# LCD.net
KiCad netlist of a schematic drawn in Altium Designer
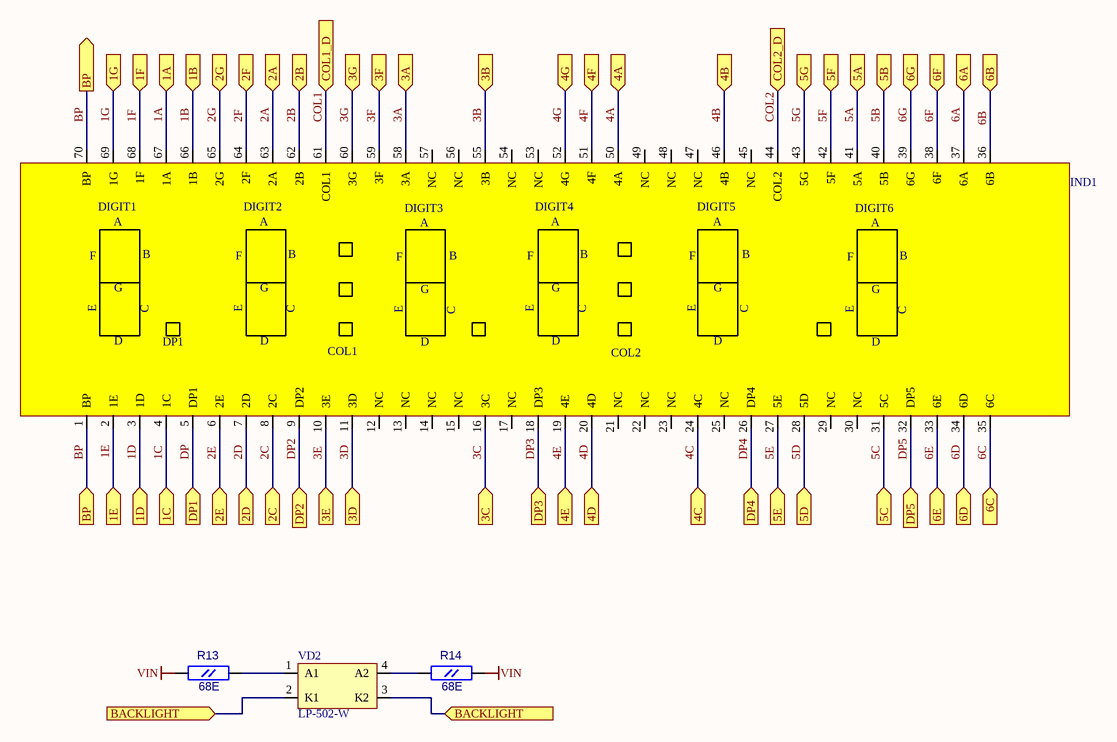
[diagram p0: LCD.SchDoc]

(export (version "E")
  (design (tool "Eeschema 10.0.6"))
  (components
    (comp (ref "IND1")
      (value "DE156")
      (footprint "IND_DE156")
      (description "6digit 7Segment indicator")
      (libsource (lib "gprs_modem_2") (part "IND7_DE156"))
    )
    (comp (ref "R13")
      (value "68E")
      (footprint "RC0603")
      (description "RC0603")
      (libsource (lib "gprs_modem_2") (part "RC0603"))
    )
    (comp (ref "R14")
      (value "68E")
      (footprint "RC0603")
      (description "RC0603")
      (libsource (lib "gprs_modem_2") (part "RC0603"))
    )
    (comp (ref "VD2")
      (value "LP-502-W")
      (footprint "LP-502-W")
      (description "Backlight for lcd display")
      (libsource (lib "gprs_modem_2") (part "LP-502-W"))
    )
  )
  (nets
    (net (code "1") (name "/1A") (class "Default")
      (node (ref "IND1") (pin "67") (pinfunction "1A_67") (pintype "passive"))
    )
    (net (code "2") (name "/1B") (class "Default")
      (node (ref "IND1") (pin "66") (pinfunction "1B_66") (pintype "passive"))
    )
    (net (code "3") (name "/1C") (class "Default")
      (node (ref "IND1") (pin "4") (pinfunction "1C_4") (pintype "passive"))
    )
    (net (code "4") (name "/1D") (class "Default")
      (node (ref "IND1") (pin "3") (pinfunction "1D_3") (pintype "passive"))
    )
    (net (code "5") (name "/1E") (class "Default")
      (node (ref "IND1") (pin "2") (pinfunction "1E_2") (pintype "passive"))
    )
    (net (code "6") (name "/1F") (class "Default")
      (node (ref "IND1") (pin "68") (pinfunction "1F_68") (pintype "passive"))
    )
    (net (code "7") (name "/1G") (class "Default")
      (node (ref "IND1") (pin "69") (pinfunction "1G_69") (pintype "passive"))
    )
    (net (code "8") (name "/2A") (class "Default")
      (node (ref "IND1") (pin "63") (pinfunction "2A_63") (pintype "passive"))
    )
    (net (code "9") (name "/2B") (class "Default")
      (node (ref "IND1") (pin "62") (pinfunction "2B_62") (pintype "passive"))
    )
    (net (code "10") (name "/2C") (class "Default")
      (node (ref "IND1") (pin "8") (pinfunction "2C_8") (pintype "passive"))
    )
    (net (code "11") (name "/2D") (class "Default")
      (node (ref "IND1") (pin "7") (pinfunction "2D_7") (pintype "passive"))
    )
    (net (code "12") (name "/2E") (class "Default")
      (node (ref "IND1") (pin "6") (pinfunction "2E_6") (pintype "passive"))
    )
    (net (code "13") (name "/2F") (class "Default")
      (node (ref "IND1") (pin "64") (pinfunction "2F_64") (pintype "passive"))
    )
    (net (code "14") (name "/2G") (class "Default")
      (node (ref "IND1") (pin "65") (pinfunction "2G_65") (pintype "passive"))
    )
    (net (code "15") (name "/3A") (class "Default")
      (node (ref "IND1") (pin "58") (pinfunction "3A_58") (pintype "passive"))
    )
    (net (code "16") (name "/3B") (class "Default")
      (node (ref "IND1") (pin "55") (pinfunction "3B_55") (pintype "passive"))
    )
    (net (code "17") (name "/3C") (class "Default")
      (node (ref "IND1") (pin "16") (pinfunction "3C_16") (pintype "passive"))
    )
    (net (code "18") (name "/3D") (class "Default")
      (node (ref "IND1") (pin "11") (pinfunction "3D_11") (pintype "passive"))
    )
    (net (code "19") (name "/3E") (class "Default")
      (node (ref "IND1") (pin "10") (pinfunction "3E_10") (pintype "passive"))
    )
    (net (code "20") (name "/3F") (class "Default")
      (node (ref "IND1") (pin "59") (pinfunction "3F_59") (pintype "passive"))
    )
    (net (code "21") (name "/3G") (class "Default")
      (node (ref "IND1") (pin "60") (pinfunction "3G_60") (pintype "passive"))
    )
    (net (code "22") (name "/4A") (class "Default")
      (node (ref "IND1") (pin "50") (pinfunction "4A_50") (pintype "passive"))
    )
    (net (code "23") (name "/4B") (class "Default")
      (node (ref "IND1") (pin "46") (pinfunction "4B_46") (pintype "passive"))
    )
    (net (code "24") (name "/4C") (class "Default")
      (node (ref "IND1") (pin "24") (pinfunction "4C_24") (pintype "passive"))
    )
    (net (code "25") (name "/4D") (class "Default")
      (node (ref "IND1") (pin "20") (pinfunction "4D_20") (pintype "passive"))
    )
    (net (code "26") (name "/4E") (class "Default")
      (node (ref "IND1") (pin "19") (pinfunction "4E_19") (pintype "passive"))
    )
    (net (code "27") (name "/4F") (class "Default")
      (node (ref "IND1") (pin "51") (pinfunction "4F_51") (pintype "passive"))
    )
    (net (code "28") (name "/4G") (class "Default")
      (node (ref "IND1") (pin "52") (pinfunction "4G_52") (pintype "passive"))
    )
    (net (code "29") (name "/5A") (class "Default")
      (node (ref "IND1") (pin "41") (pinfunction "5A_41") (pintype "passive"))
    )
    (net (code "30") (name "/5B") (class "Default")
      (node (ref "IND1") (pin "40") (pinfunction "5B_40") (pintype "passive"))
    )
    (net (code "31") (name "/5C") (class "Default")
      (node (ref "IND1") (pin "31") (pinfunction "5C_31") (pintype "passive"))
    )
    (net (code "32") (name "/5D") (class "Default")
      (node (ref "IND1") (pin "28") (pinfunction "5D_28") (pintype "passive"))
    )
    (net (code "33") (name "/5E") (class "Default")
      (node (ref "IND1") (pin "27") (pinfunction "5E_27") (pintype "passive"))
    )
    (net (code "34") (name "/5F") (class "Default")
      (node (ref "IND1") (pin "42") (pinfunction "5F_42") (pintype "passive"))
    )
    (net (code "35") (name "/5G") (class "Default")
      (node (ref "IND1") (pin "43") (pinfunction "5G_43") (pintype "passive"))
    )
    (net (code "36") (name "/6A") (class "Default")
      (node (ref "IND1") (pin "37") (pinfunction "6A_37") (pintype "passive"))
    )
    (net (code "37") (name "/6B") (class "Default")
      (node (ref "IND1") (pin "36") (pinfunction "6B_36") (pintype "passive"))
    )
    (net (code "38") (name "/6C") (class "Default")
      (node (ref "IND1") (pin "35") (pinfunction "6C_35") (pintype "passive"))
    )
    (net (code "39") (name "/6D") (class "Default")
      (node (ref "IND1") (pin "34") (pinfunction "6D_34") (pintype "passive"))
    )
    (net (code "40") (name "/6E") (class "Default")
      (node (ref "IND1") (pin "33") (pinfunction "6E_33") (pintype "passive"))
    )
    (net (code "41") (name "/6F") (class "Default")
      (node (ref "IND1") (pin "38") (pinfunction "6F_38") (pintype "passive"))
    )
    (net (code "42") (name "/6G") (class "Default")
      (node (ref "IND1") (pin "39") (pinfunction "6G_39") (pintype "passive"))
    )
    (net (code "43") (name "/BACKLIGHT") (class "Default")
      (node (ref "VD2") (pin "2") (pinfunction "K1_2") (pintype "passive"))
      (node (ref "VD2") (pin "3") (pinfunction "K2_3") (pintype "passive"))
    )
    (net (code "44") (name "/BP") (class "Default")
      (node (ref "IND1") (pin "1") (pinfunction "BP_1") (pintype "passive"))
      (node (ref "IND1") (pin "70") (pinfunction "BP_70") (pintype "passive"))
    )
    (net (code "45") (name "/COL1") (class "Default")
      (node (ref "IND1") (pin "61") (pinfunction "COL1_61") (pintype "passive"))
    )
    (net (code "46") (name "/COL2") (class "Default")
      (node (ref "IND1") (pin "44") (pinfunction "COL2_44") (pintype "passive"))
    )
    (net (code "47") (name "/DP") (class "Default")
      (node (ref "IND1") (pin "5") (pinfunction "DP1_5") (pintype "passive"))
    )
    (net (code "48") (name "/DP2") (class "Default")
      (node (ref "IND1") (pin "9") (pinfunction "DP2_9") (pintype "passive"))
    )
    (net (code "49") (name "/DP3") (class "Default")
      (node (ref "IND1") (pin "18") (pinfunction "DP3_18") (pintype "passive"))
    )
    (net (code "50") (name "/DP4") (class "Default")
      (node (ref "IND1") (pin "26") (pinfunction "DP4_26") (pintype "passive"))
    )
    (net (code "51") (name "/DP5") (class "Default")
      (node (ref "IND1") (pin "32") (pinfunction "DP5_32") (pintype "passive"))
    )
    (net (code "52") (name "Net-(R13-B)") (class "Default")
      (node (ref "R13") (pin "2") (pinfunction "B_2") (pintype "passive"))
      (node (ref "VD2") (pin "1") (pinfunction "A1_1") (pintype "passive"))
    )
    (net (code "53") (name "Net-(R14-A)") (class "Default")
      (node (ref "R14") (pin "1") (pinfunction "A_1") (pintype "passive"))
      (node (ref "VD2") (pin "4") (pinfunction "A2_4") (pintype "passive"))
    )
    (net (code "54") (name "VIN") (class "Default")
      (node (ref "R13") (pin "1") (pinfunction "A_1") (pintype "passive"))
      (node (ref "R14") (pin "2") (pinfunction "B_2") (pintype "passive"))
    )
    (net (code "55") (name "unconnected-(IND1-NC-Pad12)") (class "Default")
      (node (ref "IND1") (pin "12") (pinfunction "NC_12") (pintype "passive"))
    )
    (net (code "56") (name "unconnected-(IND1-NC-Pad13)") (class "Default")
      (node (ref "IND1") (pin "13") (pinfunction "NC_13") (pintype "passive"))
    )
    (net (code "57") (name "unconnected-(IND1-NC-Pad14)") (class "Default")
      (node (ref "IND1") (pin "14") (pinfunction "NC_14") (pintype "passive"))
    )
    (net (code "58") (name "unconnected-(IND1-NC-Pad15)") (class "Default")
      (node (ref "IND1") (pin "15") (pinfunction "NC_15") (pintype "passive"))
    )
    (net (code "59") (name "unconnected-(IND1-NC-Pad17)") (class "Default")
      (node (ref "IND1") (pin "17") (pinfunction "NC_17") (pintype "passive"))
    )
    (net (code "60") (name "unconnected-(IND1-NC-Pad21)") (class "Default")
      (node (ref "IND1") (pin "21") (pinfunction "NC_21") (pintype "passive"))
    )
    (net (code "61") (name "unconnected-(IND1-NC-Pad22)") (class "Default")
      (node (ref "IND1") (pin "22") (pinfunction "NC_22") (pintype "passive"))
    )
    (net (code "62") (name "unconnected-(IND1-NC-Pad23)") (class "Default")
      (node (ref "IND1") (pin "23") (pinfunction "NC_23") (pintype "passive"))
    )
    (net (code "63") (name "unconnected-(IND1-NC-Pad25)") (class "Default")
      (node (ref "IND1") (pin "25") (pinfunction "NC_25") (pintype "passive"))
    )
    (net (code "64") (name "unconnected-(IND1-NC-Pad29)") (class "Default")
      (node (ref "IND1") (pin "29") (pinfunction "NC_29") (pintype "passive"))
    )
    (net (code "65") (name "unconnected-(IND1-NC-Pad30)") (class "Default")
      (node (ref "IND1") (pin "30") (pinfunction "NC_30") (pintype "passive"))
    )
    (net (code "66") (name "unconnected-(IND1-NC-Pad45)") (class "Default")
      (node (ref "IND1") (pin "45") (pinfunction "NC_45") (pintype "passive"))
    )
    (net (code "67") (name "unconnected-(IND1-NC-Pad47)") (class "Default")
      (node (ref "IND1") (pin "47") (pinfunction "NC_47") (pintype "passive"))
    )
    (net (code "68") (name "unconnected-(IND1-NC-Pad48)") (class "Default")
      (node (ref "IND1") (pin "48") (pinfunction "NC_48") (pintype "passive"))
    )
    (net (code "69") (name "unconnected-(IND1-NC-Pad49)") (class "Default")
      (node (ref "IND1") (pin "49") (pinfunction "NC_49") (pintype "passive"))
    )
    (net (code "70") (name "unconnected-(IND1-NC-Pad53)") (class "Default")
      (node (ref "IND1") (pin "53") (pinfunction "NC_53") (pintype "passive"))
    )
    (net (code "71") (name "unconnected-(IND1-NC-Pad54)") (class "Default")
      (node (ref "IND1") (pin "54") (pinfunction "NC_54") (pintype "passive"))
    )
    (net (code "72") (name "unconnected-(IND1-NC-Pad56)") (class "Default")
      (node (ref "IND1") (pin "56") (pinfunction "NC_56") (pintype "passive"))
    )
    (net (code "73") (name "unconnected-(IND1-NC-Pad57)") (class "Default")
      (node (ref "IND1") (pin "57") (pinfunction "NC_57") (pintype "passive"))
    )
  )
)
